# SensorHubSchematic.net
KiCad netlist of a schematic drawn in EAGLE
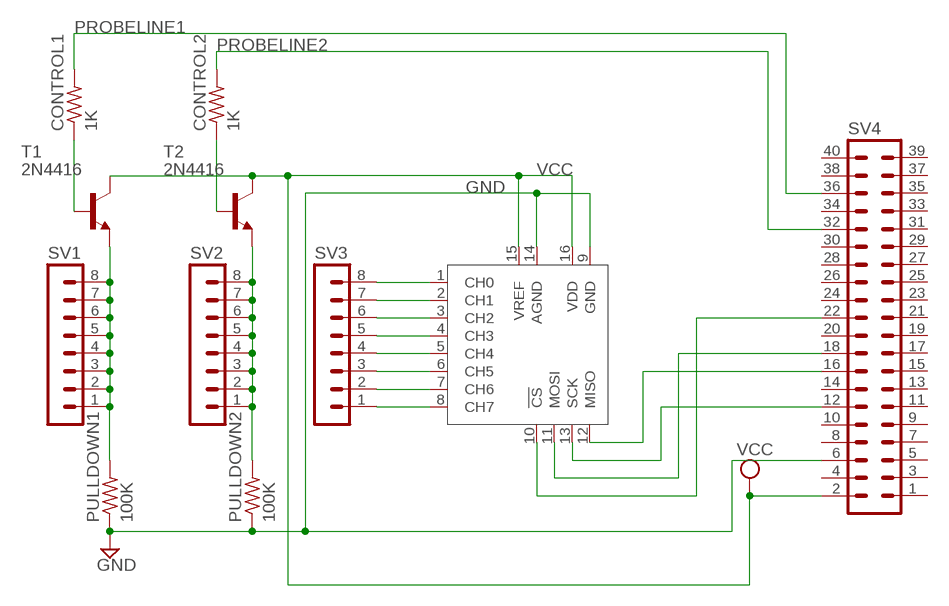
[diagram p0: schematic, sheet 1]

(export (version "E")
  (design (tool "Eeschema 10.0.6"))
  (components
    (comp (ref "CONTROL1")
      (value "1K")
      (footprint "eagle-import:0207_10")
      (libsource (lib "eagle-import") (part "R-US_0207/10"))
    )
    (comp (ref "CONTROL2")
      (value "1K")
      (footprint "eagle-import:0207_10")
      (libsource (lib "eagle-import") (part "R-US_0207/10"))
    )
    (comp (ref "PULLDOWN1")
      (value "100K")
      (footprint "eagle-import:0207_10")
      (libsource (lib "eagle-import") (part "R-US_0207/10"))
    )
    (comp (ref "PULLDOWN2")
      (value "100K")
      (footprint "eagle-import:0207_10")
      (libsource (lib "eagle-import") (part "R-US_0207/10"))
    )
    (comp (ref "SV1")
      (value "MA08-1")
      (footprint "eagle-import:MA08-1")
      (libsource (lib "eagle-import") (part "MA08-1"))
    )
    (comp (ref "SV2")
      (value "MA08-1")
      (footprint "eagle-import:MA08-1")
      (libsource (lib "eagle-import") (part "MA08-1"))
    )
    (comp (ref "SV3")
      (value "MA08-1")
      (footprint "eagle-import:MA08-1")
      (libsource (lib "eagle-import") (part "MA08-1"))
    )
    (comp (ref "SV4")
      (value "MA20-2")
      (footprint "eagle-import:MA20-2")
      (libsource (lib "eagle-import") (part "MA20-2"))
    )
    (comp (ref "T1")
      (value "2N4416")
      (footprint "eagle-import:TO92")
      (libsource (lib "eagle-import") (part "2N4416"))
    )
    (comp (ref "T2")
      (value "2N4416")
      (footprint "eagle-import:TO92")
      (libsource (lib "eagle-import") (part "2N4416"))
    )
    (comp (ref "U$1")
      (value "MCP3008P")
      (footprint "eagle-import:DIL16")
      (libsource (lib "eagle-import") (part "MCP3008P"))
    )
  )
  (nets
    (net (code "1") (name "/PROBELINE1") (class "Default")
      (node (ref "CONTROL1") (pin "2") (pinfunction "2_2") (pintype "passive"))
      (node (ref "SV4") (pin "36") (pinfunction "36_36") (pintype "passive"))
    )
    (net (code "2") (name "/PROBELINE2") (class "Default")
      (node (ref "CONTROL2") (pin "2") (pinfunction "2_2") (pintype "passive"))
      (node (ref "SV4") (pin "32") (pinfunction "32_32") (pintype "passive"))
    )
    (net (code "3") (name "GND") (class "Default")
      (node (ref "PULLDOWN1") (pin "1") (pinfunction "1_1") (pintype "passive"))
      (node (ref "PULLDOWN2") (pin "1") (pinfunction "1_1") (pintype "passive"))
      (node (ref "SV4") (pin "6") (pinfunction "6_6") (pintype "passive"))
      (node (ref "U$1") (pin "14") (pinfunction "AGND_14") (pintype "power_in"))
      (node (ref "U$1") (pin "9") (pinfunction "GND_9") (pintype "power_in"))
    )
    (net (code "4") (name "Net-(T1-B)") (class "Default")
      (node (ref "CONTROL1") (pin "1") (pinfunction "1_1") (pintype "passive"))
      (node (ref "T1") (pin "2") (pinfunction "B_2") (pintype "passive"))
    )
    (net (code "5") (name "Net-(T1-E)") (class "Default")
      (node (ref "PULLDOWN1") (pin "2") (pinfunction "2_2") (pintype "passive"))
      (node (ref "SV1") (pin "1") (pinfunction "1_1") (pintype "passive"))
      (node (ref "SV1") (pin "2") (pinfunction "2_2") (pintype "passive"))
      (node (ref "SV1") (pin "3") (pinfunction "3_3") (pintype "passive"))
      (node (ref "SV1") (pin "4") (pinfunction "4_4") (pintype "passive"))
      (node (ref "SV1") (pin "5") (pinfunction "5_5") (pintype "passive"))
      (node (ref "SV1") (pin "6") (pinfunction "6_6") (pintype "passive"))
      (node (ref "SV1") (pin "7") (pinfunction "7_7") (pintype "passive"))
      (node (ref "SV1") (pin "8") (pinfunction "8_8") (pintype "passive"))
      (node (ref "T1") (pin "3") (pinfunction "E_3") (pintype "passive"))
    )
    (net (code "6") (name "Net-(T2-B)") (class "Default")
      (node (ref "CONTROL2") (pin "1") (pinfunction "1_1") (pintype "passive"))
      (node (ref "T2") (pin "2") (pinfunction "B_2") (pintype "passive"))
    )
    (net (code "7") (name "Net-(T2-E)") (class "Default")
      (node (ref "PULLDOWN2") (pin "2") (pinfunction "2_2") (pintype "passive"))
      (node (ref "SV2") (pin "1") (pinfunction "1_1") (pintype "passive"))
      (node (ref "SV2") (pin "2") (pinfunction "2_2") (pintype "passive"))
      (node (ref "SV2") (pin "3") (pinfunction "3_3") (pintype "passive"))
      (node (ref "SV2") (pin "4") (pinfunction "4_4") (pintype "passive"))
      (node (ref "SV2") (pin "5") (pinfunction "5_5") (pintype "passive"))
      (node (ref "SV2") (pin "6") (pinfunction "6_6") (pintype "passive"))
      (node (ref "SV2") (pin "7") (pinfunction "7_7") (pintype "passive"))
      (node (ref "SV2") (pin "8") (pinfunction "8_8") (pintype "passive"))
      (node (ref "T2") (pin "3") (pinfunction "E_3") (pintype "passive"))
    )
    (net (code "8") (name "Net-(U$1-CH0)") (class "Default")
      (node (ref "SV3") (pin "8") (pinfunction "8_8") (pintype "passive"))
      (node (ref "U$1") (pin "1") (pinfunction "CH0_1") (pintype "input"))
    )
    (net (code "9") (name "Net-(U$1-CH1)") (class "Default")
      (node (ref "SV3") (pin "7") (pinfunction "7_7") (pintype "passive"))
      (node (ref "U$1") (pin "2") (pinfunction "CH1_2") (pintype "input"))
    )
    (net (code "10") (name "Net-(U$1-CH2)") (class "Default")
      (node (ref "SV3") (pin "6") (pinfunction "6_6") (pintype "passive"))
      (node (ref "U$1") (pin "3") (pinfunction "CH2_3") (pintype "input"))
    )
    (net (code "11") (name "Net-(U$1-CH3)") (class "Default")
      (node (ref "SV3") (pin "5") (pinfunction "5_5") (pintype "passive"))
      (node (ref "U$1") (pin "4") (pinfunction "CH3_4") (pintype "input"))
    )
    (net (code "12") (name "Net-(U$1-CH4)") (class "Default")
      (node (ref "SV3") (pin "4") (pinfunction "4_4") (pintype "passive"))
      (node (ref "U$1") (pin "5") (pinfunction "CH4_5") (pintype "input"))
    )
    (net (code "13") (name "Net-(U$1-CH5)") (class "Default")
      (node (ref "SV3") (pin "3") (pinfunction "3_3") (pintype "passive"))
      (node (ref "U$1") (pin "6") (pinfunction "CH5_6") (pintype "input"))
    )
    (net (code "14") (name "Net-(U$1-CH6)") (class "Default")
      (node (ref "SV3") (pin "2") (pinfunction "2_2") (pintype "passive"))
      (node (ref "U$1") (pin "7") (pinfunction "CH6_7") (pintype "input"))
    )
    (net (code "15") (name "Net-(U$1-CH7)") (class "Default")
      (node (ref "SV3") (pin "1") (pinfunction "1_1") (pintype "passive"))
      (node (ref "U$1") (pin "8") (pinfunction "CH7_8") (pintype "input"))
    )
    (net (code "16") (name "Net-(U$1-MISO)") (class "Default")
      (node (ref "SV4") (pin "16") (pinfunction "16_16") (pintype "passive"))
      (node (ref "U$1") (pin "12") (pinfunction "MISO_12") (pintype "output"))
    )
    (net (code "17") (name "Net-(U$1-MOSI)") (class "Default")
      (node (ref "SV4") (pin "18") (pinfunction "18_18") (pintype "passive"))
      (node (ref "U$1") (pin "11") (pinfunction "MOSI_11") (pintype "input"))
    )
    (net (code "18") (name "Net-(U$1-SCK)") (class "Default")
      (node (ref "SV4") (pin "12") (pinfunction "12_12") (pintype "passive"))
      (node (ref "U$1") (pin "13") (pinfunction "SCK_13") (pintype "input"))
    )
    (net (code "19") (name "Net-(U$1-~{CS})") (class "Default")
      (node (ref "SV4") (pin "22") (pinfunction "22_22") (pintype "passive"))
      (node (ref "U$1") (pin "10") (pinfunction "~{CS}_10") (pintype "input"))
    )
    (net (code "20") (name "VCC") (class "Default")
      (node (ref "SV4") (pin "2") (pinfunction "2_2") (pintype "passive"))
      (node (ref "T1") (pin "1") (pinfunction "C_1") (pintype "passive"))
      (node (ref "T2") (pin "1") (pinfunction "C_1") (pintype "passive"))
      (node (ref "U$1") (pin "15") (pinfunction "VREF_15") (pintype "power_in"))
      (node (ref "U$1") (pin "16") (pinfunction "VDD_16") (pintype "power_in"))
    )
    (net (code "21") (name "unconnected-(SV4-Pad1)") (class "Default")
      (node (ref "SV4") (pin "1") (pinfunction "1_1") (pintype "passive"))
    )
    (net (code "22") (name "unconnected-(SV4-Pad3)") (class "Default")
      (node (ref "SV4") (pin "3") (pinfunction "3_3") (pintype "passive"))
    )
    (net (code "23") (name "unconnected-(SV4-Pad4)") (class "Default")
      (node (ref "SV4") (pin "4") (pinfunction "4_4") (pintype "passive"))
    )
    (net (code "24") (name "unconnected-(SV4-Pad5)") (class "Default")
      (node (ref "SV4") (pin "5") (pinfunction "5_5") (pintype "passive"))
    )
    (net (code "25") (name "unconnected-(SV4-Pad7)") (class "Default")
      (node (ref "SV4") (pin "7") (pinfunction "7_7") (pintype "passive"))
    )
    (net (code "26") (name "unconnected-(SV4-Pad8)") (class "Default")
      (node (ref "SV4") (pin "8") (pinfunction "8_8") (pintype "passive"))
    )
    (net (code "27") (name "unconnected-(SV4-Pad9)") (class "Default")
      (node (ref "SV4") (pin "9") (pinfunction "9_9") (pintype "passive"))
    )
    (net (code "28") (name "unconnected-(SV4-Pad10)") (class "Default")
      (node (ref "SV4") (pin "10") (pinfunction "10_10") (pintype "passive"))
    )
    (net (code "29") (name "unconnected-(SV4-Pad11)") (class "Default")
      (node (ref "SV4") (pin "11") (pinfunction "11_11") (pintype "passive"))
    )
    (net (code "30") (name "unconnected-(SV4-Pad13)") (class "Default")
      (node (ref "SV4") (pin "13") (pinfunction "13_13") (pintype "passive"))
    )
    (net (code "31") (name "unconnected-(SV4-Pad14)") (class "Default")
      (node (ref "SV4") (pin "14") (pinfunction "14_14") (pintype "passive"))
    )
    (net (code "32") (name "unconnected-(SV4-Pad15)") (class "Default")
      (node (ref "SV4") (pin "15") (pinfunction "15_15") (pintype "passive"))
    )
    (net (code "33") (name "unconnected-(SV4-Pad17)") (class "Default")
      (node (ref "SV4") (pin "17") (pinfunction "17_17") (pintype "passive"))
    )
    (net (code "34") (name "unconnected-(SV4-Pad19)") (class "Default")
      (node (ref "SV4") (pin "19") (pinfunction "19_19") (pintype "passive"))
    )
    (net (code "35") (name "unconnected-(SV4-Pad20)") (class "Default")
      (node (ref "SV4") (pin "20") (pinfunction "20_20") (pintype "passive"))
    )
    (net (code "36") (name "unconnected-(SV4-Pad21)") (class "Default")
      (node (ref "SV4") (pin "21") (pinfunction "21_21") (pintype "passive"))
    )
    (net (code "37") (name "unconnected-(SV4-Pad23)") (class "Default")
      (node (ref "SV4") (pin "23") (pinfunction "23_23") (pintype "passive"))
    )
    (net (code "38") (name "unconnected-(SV4-Pad24)") (class "Default")
      (node (ref "SV4") (pin "24") (pinfunction "24_24") (pintype "passive"))
    )
    (net (code "39") (name "unconnected-(SV4-Pad25)") (class "Default")
      (node (ref "SV4") (pin "25") (pinfunction "25_25") (pintype "passive"))
    )
    (net (code "40") (name "unconnected-(SV4-Pad26)") (class "Default")
      (node (ref "SV4") (pin "26") (pinfunction "26_26") (pintype "passive"))
    )
    (net (code "41") (name "unconnected-(SV4-Pad27)") (class "Default")
      (node (ref "SV4") (pin "27") (pinfunction "27_27") (pintype "passive"))
    )
    (net (code "42") (name "unconnected-(SV4-Pad28)") (class "Default")
      (node (ref "SV4") (pin "28") (pinfunction "28_28") (pintype "passive"))
    )
    (net (code "43") (name "unconnected-(SV4-Pad29)") (class "Default")
      (node (ref "SV4") (pin "29") (pinfunction "29_29") (pintype "passive"))
    )
    (net (code "44") (name "unconnected-(SV4-Pad30)") (class "Default")
      (node (ref "SV4") (pin "30") (pinfunction "30_30") (pintype "passive"))
    )
    (net (code "45") (name "unconnected-(SV4-Pad31)") (class "Default")
      (node (ref "SV4") (pin "31") (pinfunction "31_31") (pintype "passive"))
    )
    (net (code "46") (name "unconnected-(SV4-Pad33)") (class "Default")
      (node (ref "SV4") (pin "33") (pinfunction "33_33") (pintype "passive"))
    )
    (net (code "47") (name "unconnected-(SV4-Pad34)") (class "Default")
      (node (ref "SV4") (pin "34") (pinfunction "34_34") (pintype "passive"))
    )
    (net (code "48") (name "unconnected-(SV4-Pad35)") (class "Default")
      (node (ref "SV4") (pin "35") (pinfunction "35_35") (pintype "passive"))
    )
    (net (code "49") (name "unconnected-(SV4-Pad37)") (class "Default")
      (node (ref "SV4") (pin "37") (pinfunction "37_37") (pintype "passive"))
    )
    (net (code "50") (name "unconnected-(SV4-Pad38)") (class "Default")
      (node (ref "SV4") (pin "38") (pinfunction "38_38") (pintype "passive"))
    )
    (net (code "51") (name "unconnected-(SV4-Pad39)") (class "Default")
      (node (ref "SV4") (pin "39") (pinfunction "39_39") (pintype "passive"))
    )
    (net (code "52") (name "unconnected-(SV4-Pad40)") (class "Default")
      (node (ref "SV4") (pin "40") (pinfunction "40_40") (pintype "passive"))
    )
  )
)
